# 04_PMIC2.net
KiCad netlist of a schematic drawn in Altium Designer
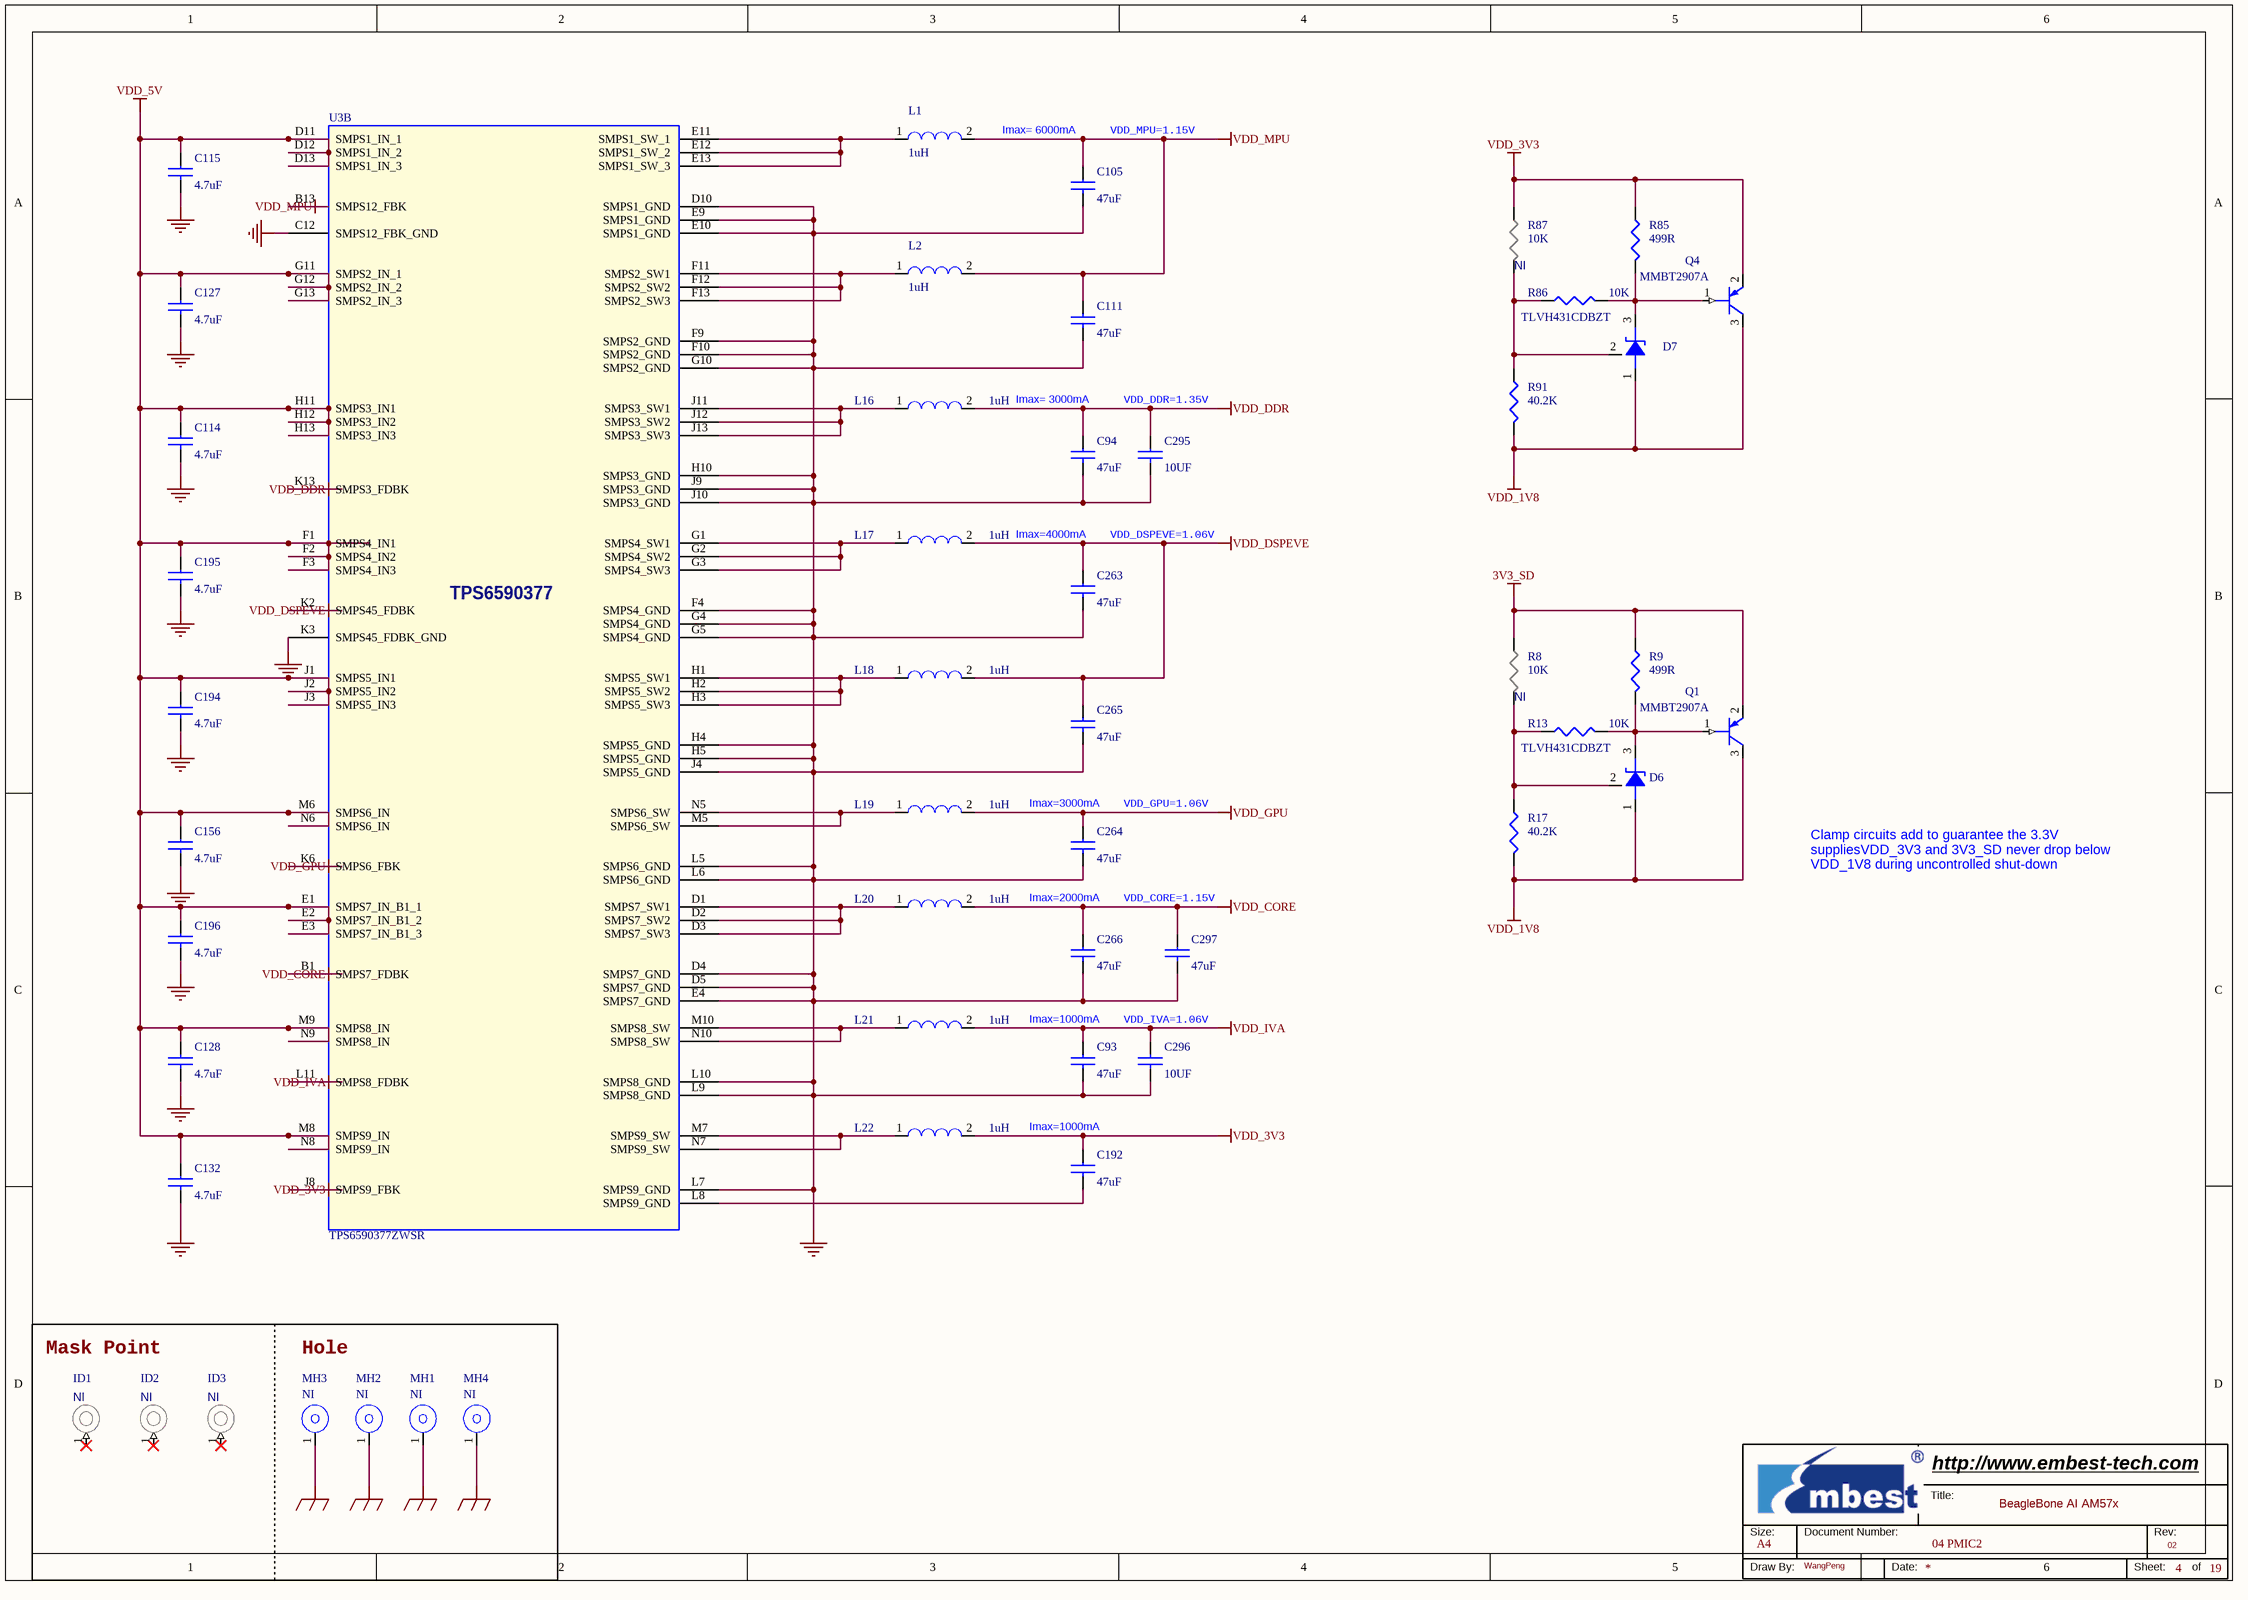
[diagram p0: 04 PMIC2.SchDoc]

(export (version "E")
  (design (tool "Eeschema 10.0.6"))
  (components
    (comp (ref "C93")
      (value "47uF")
      (footprint "C0805")
      (description "CAP,47UF,+/-20%,X5R,6.3V,SMD0805")
      (fields
        (field (name "MANUFACTURER PART NUMBER") "GRM21BR60J476ME15L")
        (field (name "MANUFACTURER") "MURATA")
      )
      (libsource (lib "*") (part "C"))
    )
    (comp (ref "C94")
      (value "47uF")
      (footprint "C0805")
      (description "CAP,47UF,+/-20%,X5R,6.3V,SMD0805")
      (fields
        (field (name "MANUFACTURER PART NUMBER") "GRM21BR60J476ME15L")
        (field (name "MANUFACTURER") "MURATA")
      )
      (libsource (lib "*") (part "C"))
    )
    (comp (ref "C105")
      (value "47uF")
      (footprint "C0805")
      (description "CAP,47UF,+/-20%,X5R,6.3V,SMD0805")
      (fields
        (field (name "MANUFACTURER PART NUMBER") "GRM21BR60J476ME15L")
        (field (name "MANUFACTURER") "MURATA")
      )
      (libsource (lib "*") (part "C"))
    )
    (comp (ref "C111")
      (value "47uF")
      (footprint "C0805")
      (description "CAP,47UF,+/-20%,X5R,6.3V,SMD0805")
      (fields
        (field (name "MANUFACTURER PART NUMBER") "GRM21BR60J476ME15L")
        (field (name "MANUFACTURER") "MURATA")
      )
      (libsource (lib "*") (part "C"))
    )
    (comp (ref "C114")
      (value "4.7uF")
      (footprint "C0603")
      (description "CAP,4.7UF,+/-10%,X5R,16V,SMD0603")
      (fields
        (field (name "MANUFACTURER PART NUMBER") "GRM188R61C475KAAJD")
        (field (name "MANUFACTURER") "Murata")
        (field (name "DATASHEET") "Y:\\新K3系统物料datasheet\\[1003_1004]capacitor-resistor 电容、电阻\\1004001100127 GRM188R61C475KAAJD murata.pdf")
      )
      (libsource (lib "*") (part "C"))
    )
    (comp (ref "C115")
      (value "4.7uF")
      (footprint "C0603")
      (description "CAP,4.7UF,+/-10%,X5R,16V,SMD0603")
      (fields
        (field (name "MANUFACTURER PART NUMBER") "GRM188R61C475KAAJD")
        (field (name "MANUFACTURER") "Murata")
        (field (name "DATASHEET") "Y:\\新K3系统物料datasheet\\[1003_1004]capacitor-resistor 电容、电阻\\1004001100127 GRM188R61C475KAAJD murata.pdf")
      )
      (libsource (lib "*") (part "C"))
    )
    (comp (ref "C127")
      (value "4.7uF")
      (footprint "C0603")
      (description "CAP,4.7UF,+/-10%,X5R,16V,SMD0603")
      (fields
        (field (name "MANUFACTURER") "Murata")
        (field (name "MANUFACTURER PART NUMBER") "GRM188R61C475KAAJD")
        (field (name "DATASHEET") "Y:\\新K3系统物料datasheet\\[1003_1004]capacitor-resistor 电容、电阻\\1004001100127 GRM188R61C475KAAJD murata.pdf")
      )
      (libsource (lib "*") (part "C"))
    )
    (comp (ref "C128")
      (value "4.7uF")
      (footprint "C0603")
      (description "CAP,4.7UF,+/-10%,X5R,16V,SMD0603")
      (fields
        (field (name "MANUFACTURER") "Murata")
        (field (name "MANUFACTURER PART NUMBER") "GRM188R61C475KAAJD")
        (field (name "DATASHEET") "Y:\\新K3系统物料datasheet\\[1003_1004]capacitor-resistor 电容、电阻\\1004001100127 GRM188R61C475KAAJD murata.pdf")
      )
      (libsource (lib "*") (part "C"))
    )
    (comp (ref "C132")
      (value "4.7uF")
      (footprint "C0603")
      (description "CAP,4.7UF,+/-10%,X5R,16V,SMD0603")
      (fields
        (field (name "MANUFACTURER PART NUMBER") "GRM188R61C475KAAJD")
        (field (name "MANUFACTURER") "Murata")
        (field (name "DATASHEET") "Y:\\新K3系统物料datasheet\\[1003_1004]capacitor-resistor 电容、电阻\\1004001100127 GRM188R61C475KAAJD murata.pdf")
      )
      (libsource (lib "*") (part "C"))
    )
    (comp (ref "C156")
      (value "4.7uF")
      (footprint "C0603")
      (description "CAP,4.7UF,+/-10%,X5R,16V,SMD0603")
      (fields
        (field (name "MANUFACTURER") "Murata")
        (field (name "MANUFACTURER PART NUMBER") "GRM188R61C475KAAJD")
        (field (name "DATASHEET") "Y:\\新K3系统物料datasheet\\[1003_1004]capacitor-resistor 电容、电阻\\1004001100127 GRM188R61C475KAAJD murata.pdf")
      )
      (libsource (lib "*") (part "C"))
    )
    (comp (ref "C192")
      (value "47uF")
      (footprint "C0805")
      (description "CAP,47UF,+/-20%,X5R,6.3V,SMD0805")
      (fields
        (field (name "MANUFACTURER PART NUMBER") "GRM21BR60J476ME15L")
        (field (name "MANUFACTURER") "MURATA")
      )
      (libsource (lib "*") (part "C"))
    )
    (comp (ref "C194")
      (value "4.7uF")
      (footprint "C0603")
      (description "CAP,4.7UF,+/-10%,X5R,16V,SMD0603")
      (fields
        (field (name "MANUFACTURER") "Murata")
        (field (name "MANUFACTURER PART NUMBER") "GRM188R61C475KAAJD")
        (field (name "DATASHEET") "Y:\\新K3系统物料datasheet\\[1003_1004]capacitor-resistor 电容、电阻\\1004001100127 GRM188R61C475KAAJD murata.pdf")
      )
      (libsource (lib "*") (part "C"))
    )
    (comp (ref "C195")
      (value "4.7uF")
      (footprint "C0603")
      (description "CAP,4.7UF,+/-10%,X5R,16V,SMD0603")
      (fields
        (field (name "MANUFACTURER") "Murata")
        (field (name "MANUFACTURER PART NUMBER") "GRM188R61C475KAAJD")
        (field (name "DATASHEET") "Y:\\新K3系统物料datasheet\\[1003_1004]capacitor-resistor 电容、电阻\\1004001100127 GRM188R61C475KAAJD murata.pdf")
      )
      (libsource (lib "*") (part "C"))
    )
    (comp (ref "C196")
      (value "4.7uF")
      (footprint "C0603")
      (description "CAP,4.7UF,+/-10%,X5R,16V,SMD0603")
      (fields
        (field (name "MANUFACTURER") "Murata")
        (field (name "MANUFACTURER PART NUMBER") "GRM188R61C475KAAJD")
        (field (name "DATASHEET") "Y:\\新K3系统物料datasheet\\[1003_1004]capacitor-resistor 电容、电阻\\1004001100127 GRM188R61C475KAAJD murata.pdf")
      )
      (libsource (lib "*") (part "C"))
    )
    (comp (ref "C263")
      (value "47uF")
      (footprint "C0805")
      (description "CAP,47UF,+/-20%,X5R,6.3V,SMD0805")
      (fields
        (field (name "MANUFACTURER PART NUMBER") "GRM21BR60J476ME15L")
        (field (name "MANUFACTURER") "MURATA")
      )
      (libsource (lib "*") (part "C"))
    )
    (comp (ref "C264")
      (value "47uF")
      (footprint "C0805")
      (description "CAP,47UF,+/-20%,X5R,6.3V,SMD0805")
      (fields
        (field (name "MANUFACTURER PART NUMBER") "GRM21BR60J476ME15L")
        (field (name "MANUFACTURER") "MURATA")
      )
      (libsource (lib "*") (part "C"))
    )
    (comp (ref "C265")
      (value "47uF")
      (footprint "C0805")
      (description "CAP,47UF,+/-20%,X5R,6.3V,SMD0805")
      (fields
        (field (name "MANUFACTURER PART NUMBER") "GRM21BR60J476ME15L")
        (field (name "MANUFACTURER") "MURATA")
      )
      (libsource (lib "*") (part "C"))
    )
    (comp (ref "C266")
      (value "47uF")
      (footprint "C0805")
      (description "CAP,47UF,+/-20%,X5R,6.3V,SMD0805")
      (fields
        (field (name "MANUFACTURER PART NUMBER") "GRM21BR60J476ME15L")
        (field (name "MANUFACTURER") "MURATA")
      )
      (libsource (lib "*") (part "C"))
    )
    (comp (ref "C295")
      (value "10UF")
      (footprint "C0603")
      (description "CAP,10UF,+/-10%,X5R,10V,SMD0603")
      (fields
        (field (name "MANUFACTURER") "Murata")
        (field (name "MANUFACTURER PART NUMBER") "GRM188R61A106KE69D")
        (field (name "DATASHEET") "Y:\\新K3系统物料datasheet\\[1003_1004]capacitor-resistor 电容、电阻\\1004001100129T2 C1608X5R1A106M.pdf")
      )
      (libsource (lib "*") (part "C"))
    )
    (comp (ref "C296")
      (value "10UF")
      (footprint "C0402")
      (description "CAP,10UF,+/-20%,X5R,6.3V,SMD0402")
      (fields
        (field (name "MANUFACTURER PART NUMBER") "CC0402MRX5R5BB106")
        (field (name "MANUFACTURER") "Yageo")
      )
      (libsource (lib "*") (part "C"))
    )
    (comp (ref "C297")
      (value "47uF")
      (footprint "C0805")
      (description "CAP,47UF,+/-20%,X5R,6.3V,SMD0805")
      (fields
        (field (name "MANUFACTURER PART NUMBER") "GRM21BR60J476ME15L")
        (field (name "MANUFACTURER") "MURATA")
      )
      (libsource (lib "*") (part "C"))
    )
    (comp (ref "D6")
      (value "TLVH431CDBZT")
      (footprint "sot95p240x120-3n")
      (description "IC,Low-Voltage Adjustable Precision Shunt Regulators")
      (fields (field (name "MANUFACTURER") "TI"))
      (libsource (lib "*") (part "DIODE ZENER_3"))
    )
    (comp (ref "D7")
      (value "TLVH431CDBZT")
      (footprint "sot95p240x120-3n")
      (description "IC,Low-Voltage Adjustable Precision Shunt Regulators")
      (fields (field (name "MANUFACTURER") "TI"))
      (libsource (lib "*") (part "DIODE ZENER_3"))
    )
    (comp (ref "ID1")
      (value "NI")
      (footprint "FD40")
      (description "MARK  point,DIA 40mil")
      (fields (field (name "ASSY") "NI"))
      (libsource (lib "*") (part "MARK POINT"))
    )
    (comp (ref "ID2")
      (value "NI")
      (footprint "FD40")
      (description "MARK  point,DIA 40mil")
      (fields (field (name "ASSY") "NI"))
      (libsource (lib "*") (part "MARK POINT"))
    )
    (comp (ref "ID3")
      (value "NI")
      (footprint "FD40")
      (description "MARK  point,DIA 40mil")
      (fields (field (name "ASSY") "NI"))
      (libsource (lib "*") (part "MARK POINT"))
    )
    (comp (ref "L1")
      (value "1uH")
      (footprint "L40X40_B")
      (description "Power Inductor,Magnetic shielded,1uH,idc4.5A,27mohm,4.3x4.0x2.0mm,20%,SMD,TR")
      (fields
        (field (name "MANUFACTURER PART NUMBER") "SP04O203M1U")
        (field (name "MANUFACTURER") "GAUSSTEK")
        (field (name "DATASHEET") "Y:\\新K3系统物料datasheet\\[1005]beads-inductors 磁珠、电感\\1005004100077 S-英蓓特SP04O203M1U.pdf")
      )
      (libsource (lib "*") (part "L"))
    )
    (comp (ref "L2")
      (value "1uH")
      (footprint "L40X40_B")
      (description "Power Inductor,Magnetic shielded,1uH,idc4.5A,27mohm,4.3x4.0x2.0mm,20%,SMD,TR")
      (fields
        (field (name "MANUFACTURER") "GAUSSTEK")
        (field (name "MANUFACTURER PART NUMBER") "SP04O203M1U")
        (field (name "DATASHEET") "Y:\\新K3系统物料datasheet\\[1005]beads-inductors 磁珠、电感\\1005004100077 S-英蓓特SP04O203M1U.pdf")
      )
      (libsource (lib "*") (part "L"))
    )
    (comp (ref "L16")
      (value "1uH")
      (footprint "INDPW250X200X105N")
      (fields
        (field (name "MANUFACTURER") "Gausstek")
        (field (name "MANUFACTURER PART NUMBER") "DI20A102M1U")
        (field (name "DATASHEET") "Y:\\新K3系统物料datasheet\\[1005]beads-inductors 磁珠、电感\\1005001100194 DI20A102M1U.pdf")
      )
      (libsource (lib "*") (part "L"))
    )
    (comp (ref "L17")
      (value "1uH")
      (footprint "INDPW250X200X105N")
      (fields
        (field (name "MANUFACTURER PART NUMBER") "DI20A102M1U")
        (field (name "MANUFACTURER") "Gausstek")
        (field (name "DATASHEET") "Y:\\新K3系统物料datasheet\\[1005]beads-inductors 磁珠、电感\\1005001100194 DI20A102M1U.pdf")
      )
      (libsource (lib "*") (part "L"))
    )
    (comp (ref "L18")
      (value "1uH")
      (footprint "INDPW250X200X105N")
      (fields
        (field (name "MANUFACTURER") "Gausstek")
        (field (name "MANUFACTURER PART NUMBER") "DI20A102M1U")
        (field (name "DATASHEET") "Y:\\新K3系统物料datasheet\\[1005]beads-inductors 磁珠、电感\\1005001100194 DI20A102M1U.pdf")
      )
      (libsource (lib "*") (part "L"))
    )
    (comp (ref "L19")
      (value "1uH")
      (footprint "INDPW250X200X105N")
      (fields
        (field (name "MANUFACTURER PART NUMBER") "DI20A102M1U")
        (field (name "MANUFACTURER") "Gausstek")
        (field (name "DATASHEET") "Y:\\新K3系统物料datasheet\\[1005]beads-inductors 磁珠、电感\\1005001100194 DI20A102M1U.pdf")
      )
      (libsource (lib "*") (part "L"))
    )
    (comp (ref "L20")
      (value "1uH")
      (footprint "INDPW250X200X105N")
      (fields
        (field (name "MANUFACTURER") "Gausstek")
        (field (name "MANUFACTURER PART NUMBER") "DI20A102M1U")
        (field (name "DATASHEET") "Y:\\新K3系统物料datasheet\\[1005]beads-inductors 磁珠、电感\\1005001100194 DI20A102M1U.pdf")
      )
      (libsource (lib "*") (part "L"))
    )
    (comp (ref "L21")
      (value "1uH")
      (footprint "INDPW250X200X105N")
      (fields
        (field (name "MANUFACTURER PART NUMBER") "DI20A102M1U")
        (field (name "MANUFACTURER") "Gausstek")
        (field (name "DATASHEET") "Y:\\新K3系统物料datasheet\\[1005]beads-inductors 磁珠、电感\\1005001100194 DI20A102M1U.pdf")
      )
      (libsource (lib "*") (part "L"))
    )
    (comp (ref "L22")
      (value "1uH")
      (footprint "INDPW250X200X105N")
      (fields
        (field (name "MANUFACTURER") "Gausstek")
        (field (name "MANUFACTURER PART NUMBER") "DI20A102M1U")
        (field (name "DATASHEET") "Y:\\新K3系统物料datasheet\\[1005]beads-inductors 磁珠、电感\\1005001100194 DI20A102M1U.pdf")
      )
      (libsource (lib "*") (part "L"))
    )
    (comp (ref "MH1")
      (value "NI")
      (footprint "MTGH200C125D_PL")
      (description "Plated hole,Circle,DAI 4.445MM ,VIA 3.175MM")
      (libsource (lib "*") (part "METALLIC HOLE"))
    )
    (comp (ref "MH2")
      (value "NI")
      (footprint "MTGH200C125D_PL")
      (description "Plated hole,Circle,DAI 4.445MM ,VIA 3.175MM")
      (libsource (lib "*") (part "METALLIC HOLE"))
    )
    (comp (ref "MH3")
      (value "NI")
      (footprint "MTGH200C125D_PL")
      (description "Plated hole,Circle,DAI 4.445MM ,VIA 3.175MM")
      (libsource (lib "*") (part "METALLIC HOLE"))
    )
    (comp (ref "MH4")
      (value "NI")
      (footprint "MTGH200C125D_PL")
      (description "Plated hole,Circle,DAI 4.445MM ,VIA 3.175MM")
      (libsource (lib "*") (part "METALLIC HOLE"))
    )
    (comp (ref "Q1")
      (value "MMBT2907A")
      (footprint "SOT23_123")
      (description "Transistor,PNP,MMBT2907A-7-F,60V,600MA,SOT-23,SMD")
      (fields
        (field (name "MANUFACTURER") "Diodes")
        (field (name "MANUFACTURER PART NUMBER") "MMBT2907A-7-F")
        (field (name "DATASHEET") "Y:\\新K3系统物料datasheet\\[1006002~013]diodes-transistors 二三极管\\1006012100001 Diodes MMBT2907A-7-F.pdf")
      )
      (libsource (lib "*") (part "PNP"))
    )
    (comp (ref "Q4")
      (value "MMBT2907A")
      (footprint "SOT23_123")
      (description "Transistor,PNP,MMBT2907A-7-F,60V,600MA,SOT-23,SMD")
      (fields
        (field (name "MANUFACTURER") "Diodes")
        (field (name "MANUFACTURER PART NUMBER") "MMBT2907A-7-F")
        (field (name "DATASHEET") "Y:\\新K3系统物料datasheet\\[1006002~013]diodes-transistors 二三极管\\1006012100001 Diodes MMBT2907A-7-F.pdf")
      )
      (libsource (lib "*") (part "PNP"))
    )
    (comp (ref "R8")
      (value "10K")
      (footprint "R0402")
      (description "RES,10K,+/-1%,1/16W,SMD0402")
      (fields
        (field (name "ASSY") "NI")
        (field (name "MANUFACTURER PART NUMBER") "RC0402FR-0710KL")
        (field (name "MANUFACTURER") "YAGEO")
      )
      (libsource (lib "*") (part "R"))
    )
    (comp (ref "R9")
      (value "499R")
      (footprint "R0402")
      (description "RES,499R,+/-1%,1/16W,SMD0402")
      (fields
        (field (name "MANUFACTURER") "YAGEO")
        (field (name "MANUFACTURER PART NUMBER") "RC0402FR-07499RL")
      )
      (libsource (lib "*") (part "R"))
    )
    (comp (ref "R13")
      (value "10K")
      (footprint "R0402")
      (description "RES,10K,+/-1%,1/16W,SMD0402")
      (fields
        (field (name "MANUFACTURER PART NUMBER") "RC0402FR-0710KL")
        (field (name "MANUFACTURER") "YAGEO")
      )
      (libsource (lib "*") (part "R"))
    )
    (comp (ref "R17")
      (value "40.2K")
      (footprint "R0402")
      (description "RES,40K2,+/-1%,1/16W,SMD0402")
      (fields
        (field (name "MANUFACTURER") "YAGEO")
        (field (name "MANUFACTURER PART NUMBER") "RC0402FR-0740K2L")
      )
      (libsource (lib "*") (part "R"))
    )
    (comp (ref "R85")
      (value "499R")
      (footprint "R0402")
      (description "RES,499R,+/-1%,1/16W,SMD0402")
      (fields
        (field (name "MANUFACTURER") "YAGEO")
        (field (name "MANUFACTURER PART NUMBER") "RC0402FR-07499RL")
      )
      (libsource (lib "*") (part "R"))
    )
    (comp (ref "R86")
      (value "10K")
      (footprint "R0402")
      (description "RES,10K,+/-1%,1/16W,SMD0402")
      (fields
        (field (name "MANUFACTURER PART NUMBER") "RC0402FR-0710KL")
        (field (name "MANUFACTURER") "YAGEO")
      )
      (libsource (lib "*") (part "R"))
    )
    (comp (ref "R87")
      (value "10K")
      (footprint "R0402")
      (description "RES,10K,+/-1%,1/16W,SMD0402")
      (fields
        (field (name "ASSY") "NI")
        (field (name "MANUFACTURER PART NUMBER") "RC0402FR-0710KL")
        (field (name "MANUFACTURER") "YAGEO")
      )
      (libsource (lib "*") (part "R"))
    )
    (comp (ref "R91")
      (value "40.2K")
      (footprint "R0402")
      (description "RES,40K2,+/-1%,1/16W,SMD0402")
      (fields
        (field (name "MANUFACTURER") "YAGEO")
        (field (name "MANUFACTURER PART NUMBER") "RC0402FR-0740K2L")
      )
      (libsource (lib "*") (part "R"))
    )
    (comp (ref "U3")
      (value "TPS6590377ZWSR")
      (footprint "bga12x12-169-55m")
      (description "IC TPS659037 Power Management Unit (PMU) for Processor NFBGA-169 SMD")
      (fields
        (field (name "MANUFACTURER") "TI")
        (field (name "DATASHEET") "Y:\\新K3系统物料datasheet\\[1002]IC 集成电路\\1002004100230 [TPS6590377ZWSR] tps659037.pdf")
      )
      (libsource (lib "*") (part "TPS659037"))
    )
  )
  (nets
    (net (code "1") (name "3V3_SD") (class "Default")
      (node (ref "Q1") (pin "2") (pinfunction "E_2") (pintype "passive"))
      (node (ref "R8") (pin "1") (pinfunction "1_1") (pintype "passive"))
      (node (ref "R9") (pin "1") (pinfunction "1_1") (pintype "passive"))
    )
    (net (code "2") (name "GND") (class "Default")
      (node (ref "C105") (pin "2") (pinfunction "2_2") (pintype "passive"))
      (node (ref "C111") (pin "2") (pinfunction "2_2") (pintype "passive"))
      (node (ref "C114") (pin "2") (pinfunction "2_2") (pintype "passive"))
      (node (ref "C115") (pin "2") (pinfunction "2_2") (pintype "passive"))
      (node (ref "C127") (pin "2") (pinfunction "2_2") (pintype "passive"))
      (node (ref "C128") (pin "2") (pinfunction "2_2") (pintype "passive"))
      (node (ref "C132") (pin "2") (pinfunction "2_2") (pintype "passive"))
      (node (ref "C156") (pin "2") (pinfunction "2_2") (pintype "passive"))
      (node (ref "C194") (pin "2") (pinfunction "2_2") (pintype "passive"))
      (node (ref "C195") (pin "2") (pinfunction "2_2") (pintype "passive"))
      (node (ref "C196") (pin "2") (pinfunction "2_2") (pintype "passive"))
      (node (ref "C263") (pin "2") (pinfunction "2_2") (pintype "passive"))
      (node (ref "C264") (pin "2") (pinfunction "2_2") (pintype "passive"))
      (node (ref "C265") (pin "2") (pinfunction "2_2") (pintype "passive"))
      (node (ref "C266") (pin "2") (pinfunction "2_2") (pintype "passive"))
      (node (ref "C295") (pin "2") (pinfunction "2_2") (pintype "passive"))
      (node (ref "C296") (pin "2") (pinfunction "2_2") (pintype "passive"))
      (node (ref "C297") (pin "2") (pinfunction "2_2") (pintype "passive"))
      (node (ref "C93") (pin "2") (pinfunction "2_2") (pintype "passive"))
      (node (ref "C94") (pin "2") (pinfunction "2_2") (pintype "passive"))
      (node (ref "U3") (pin "C12") (pinfunction "SMPS12_FBK_GND_C12") (pintype "passive"))
      (node (ref "U3") (pin "D10") (pinfunction "SMPS1_GND_D10") (pintype "power_in"))
      (node (ref "U3") (pin "D4") (pinfunction "SMPS7_GND_D4") (pintype "power_in"))
      (node (ref "U3") (pin "D5") (pinfunction "SMPS7_GND_D5") (pintype "power_in"))
      (node (ref "U3") (pin "E10") (pinfunction "SMPS1_GND_E10") (pintype "power_in"))
      (node (ref "U3") (pin "E4") (pinfunction "SMPS7_GND_E4") (pintype "power_in"))
      (node (ref "U3") (pin "E9") (pinfunction "SMPS1_GND_E9") (pintype "power_in"))
      (node (ref "U3") (pin "F10") (pinfunction "SMPS2_GND_F10") (pintype "power_in"))
      (node (ref "U3") (pin "F4") (pinfunction "SMPS4_GND_F4") (pintype "power_in"))
      (node (ref "U3") (pin "F9") (pinfunction "SMPS2_GND_F9") (pintype "power_in"))
      (node (ref "U3") (pin "G10") (pinfunction "SMPS2_GND_G10") (pintype "power_in"))
      (node (ref "U3") (pin "G4") (pinfunction "SMPS4_GND_G4") (pintype "power_in"))
      (node (ref "U3") (pin "G5") (pinfunction "SMPS4_GND_G5") (pintype "power_in"))
      (node (ref "U3") (pin "H10") (pinfunction "SMPS3_GND_H10") (pintype "power_in"))
      (node (ref "U3") (pin "H4") (pinfunction "SMPS5_GND_H4") (pintype "power_in"))
      (node (ref "U3") (pin "H5") (pinfunction "SMPS5_GND_H5") (pintype "power_in"))
      (node (ref "U3") (pin "J10") (pinfunction "SMPS3_GND_J10") (pintype "power_in"))
      (node (ref "U3") (pin "J4") (pinfunction "SMPS5_GND_J4") (pintype "power_in"))
      (node (ref "U3") (pin "J9") (pinfunction "SMPS3_GND_J9") (pintype "power_in"))
      (node (ref "U3") (pin "K3") (pinfunction "SMPS45_FDBK_GND_K3") (pintype "passive"))
      (node (ref "U3") (pin "L10") (pinfunction "SMPS8_GND_L10") (pintype "power_in"))
      (node (ref "U3") (pin "L5") (pinfunction "SMPS6_GND_L5") (pintype "power_in"))
      (node (ref "U3") (pin "L6") (pinfunction "SMPS6_GND_L6") (pintype "power_in"))
      (node (ref "U3") (pin "L7") (pinfunction "SMPS9_GND_L7") (pintype "power_in"))
      (node (ref "U3") (pin "L9") (pinfunction "SMPS8_GND_L9") (pintype "power_in"))
    )
    (net (code "3") (name "GND_EARTH") (class "Default")
      (node (ref "MH1") (pin "1") (pinfunction "1_1") (pintype "passive"))
      (node (ref "MH2") (pin "1") (pinfunction "1_1") (pintype "passive"))
      (node (ref "MH3") (pin "1") (pinfunction "1_1") (pintype "passive"))
      (node (ref "MH4") (pin "1") (pinfunction "1_1") (pintype "passive"))
    )
    (net (code "4") (name "Net-(C192-Pad2)") (class "Default")
      (node (ref "C192") (pin "2") (pinfunction "2_2") (pintype "passive"))
      (node (ref "U3") (pin "L8") (pinfunction "SMPS9_GND_L8") (pintype "power_in"))
    )
    (net (code "5") (name "Net-(D6-K)") (class "Default")
      (node (ref "D6") (pin "3") (pinfunction "K_3") (pintype "passive"))
      (node (ref "Q1") (pin "1") (pinfunction "B_1") (pintype "input"))
      (node (ref "R13") (pin "2") (pinfunction "2_2") (pintype "passive"))
      (node (ref "R9") (pin "2") (pinfunction "2_2") (pintype "passive"))
    )
    (net (code "6") (name "Net-(D6-NC)") (class "Default")
      (node (ref "D6") (pin "2") (pinfunction "NC_2") (pintype "passive"))
      (node (ref "R13") (pin "1") (pinfunction "1_1") (pintype "passive"))
      (node (ref "R17") (pin "1") (pinfunction "1_1") (pintype "passive"))
      (node (ref "R8") (pin "2") (pinfunction "2_2") (pintype "passive"))
    )
    (net (code "7") (name "Net-(D7-K)") (class "Default")
      (node (ref "D7") (pin "3") (pinfunction "K_3") (pintype "passive"))
      (node (ref "Q4") (pin "1") (pinfunction "B_1") (pintype "input"))
      (node (ref "R85") (pin "2") (pinfunction "2_2") (pintype "passive"))
      (node (ref "R86") (pin "2") (pinfunction "2_2") (pintype "passive"))
    )
    (net (code "8") (name "Net-(D7-NC)") (class "Default")
      (node (ref "D7") (pin "2") (pinfunction "NC_2") (pintype "passive"))
      (node (ref "R86") (pin "1") (pinfunction "1_1") (pintype "passive"))
      (node (ref "R87") (pin "2") (pinfunction "2_2") (pintype "passive"))
      (node (ref "R91") (pin "1") (pinfunction "1_1") (pintype "passive"))
    )
    (net (code "9") (name "Net-(L19-Pad1)") (class "Default")
      (node (ref "L19") (pin "1") (pinfunction "1_1") (pintype "passive"))
      (node (ref "U3") (pin "M5") (pinfunction "SMPS6_SW_M5") (pintype "power_in"))
      (node (ref "U3") (pin "N5") (pinfunction "SMPS6_SW_N5") (pintype "power_in"))
    )
    (net (code "10") (name "Net-(L21-Pad1)") (class "Default")
      (node (ref "L21") (pin "1") (pinfunction "1_1") (pintype "passive"))
      (node (ref "U3") (pin "M10") (pinfunction "SMPS8_SW_M10") (pintype "power_in"))
      (node (ref "U3") (pin "N10") (pinfunction "SMPS8_SW_N10") (pintype "power_in"))
    )
    (net (code "11") (name "Net-(L22-Pad1)") (class "Default")
      (node (ref "L22") (pin "1") (pinfunction "1_1") (pintype "passive"))
      (node (ref "U3") (pin "M7") (pinfunction "SMPS9_SW_M7") (pintype "power_in"))
      (node (ref "U3") (pin "N7") (pinfunction "SMPS9_SW_N7") (pintype "power_in"))
    )
    (net (code "12") (name "Net-(U3B-SMPS1_SW_1)") (class "Default")
      (node (ref "L1") (pin "1") (pinfunction "1_1") (pintype "passive"))
      (node (ref "U3") (pin "E11") (pinfunction "SMPS1_SW_1_E11") (pintype "passive"))
      (node (ref "U3") (pin "E12") (pinfunction "SMPS1_SW_2_E12") (pintype "passive"))
      (node (ref "U3") (pin "E13") (pinfunction "SMPS1_SW_3_E13") (pintype "passive"))
    )
    (net (code "13") (name "Net-(U3B-SMPS2_SW1)") (class "Default")
      (node (ref "L2") (pin "1") (pinfunction "1_1") (pintype "passive"))
      (node (ref "U3") (pin "F11") (pinfunction "SMPS2_SW1_F11") (pintype "passive"))
      (node (ref "U3") (pin "F12") (pinfunction "SMPS2_SW2_F12") (pintype "passive"))
      (node (ref "U3") (pin "F13") (pinfunction "SMPS2_SW3_F13") (pintype "passive"))
    )
    (net (code "14") (name "Net-(U3B-SMPS3_SW1)") (class "Default")
      (node (ref "L16") (pin "1") (pinfunction "1_1") (pintype "passive"))
      (node (ref "U3") (pin "J11") (pinfunction "SMPS3_SW1_J11") (pintype "passive"))
      (node (ref "U3") (pin "J12") (pinfunction "SMPS3_SW2_J12") (pintype "passive"))
      (node (ref "U3") (pin "J13") (pinfunction "SMPS3_SW3_J13") (pintype "passive"))
    )
    (net (code "15") (name "Net-(U3B-SMPS4_SW1)") (class "Default")
      (node (ref "L17") (pin "1") (pinfunction "1_1") (pintype "passive"))
      (node (ref "U3") (pin "G1") (pinfunction "SMPS4_SW1_G1") (pintype "passive"))
      (node (ref "U3") (pin "G2") (pinfunction "SMPS4_SW2_G2") (pintype "passive"))
      (node (ref "U3") (pin "G3") (pinfunction "SMPS4_SW3_G3") (pintype "passive"))
    )
    (net (code "16") (name "Net-(U3B-SMPS5_SW1)") (class "Default")
      (node (ref "L18") (pin "1") (pinfunction "1_1") (pintype "passive"))
      (node (ref "U3") (pin "H1") (pinfunction "SMPS5_SW1_H1") (pintype "passive"))
      (node (ref "U3") (pin "H2") (pinfunction "SMPS5_SW2_H2") (pintype "passive"))
      (node (ref "U3") (pin "H3") (pinfunction "SMPS5_SW3_H3") (pintype "passive"))
    )
    (net (code "17") (name "Net-(U3B-SMPS7_SW1)") (class "Default")
      (node (ref "L20") (pin "1") (pinfunction "1_1") (pintype "passive"))
      (node (ref "U3") (pin "D1") (pinfunction "SMPS7_SW1_D1") (pintype "power_in"))
      (node (ref "U3") (pin "D2") (pinfunction "SMPS7_SW2_D2") (pintype "power_in"))
      (node (ref "U3") (pin "D3") (pinfunction "SMPS7_SW3_D3") (pintype "power_in"))
    )
    (net (code "18") (name "VDD_1V8") (class "Default")
      (node (ref "D6") (pin "1") (pinfunction "A_1") (pintype "passive"))
      (node (ref "D7") (pin "1") (pinfunction "A_1") (pintype "passive"))
      (node (ref "Q1") (pin "3") (pinfunction "C_3") (pintype "passive"))
      (node (ref "Q4") (pin "3") (pinfunction "C_3") (pintype "passive"))
      (node (ref "R17") (pin "2") (pinfunction "2_2") (pintype "passive"))
      (node (ref "R91") (pin "2") (pinfunction "2_2") (pintype "passive"))
    )
    (net (code "19") (name "VDD_3V3") (class "Default")
      (node (ref "C192") (pin "1") (pinfunction "1_1") (pintype "passive"))
      (node (ref "L22") (pin "2") (pinfunction "2_2") (pintype "passive"))
      (node (ref "Q4") (pin "2") (pinfunction "E_2") (pintype "passive"))
      (node (ref "R85") (pin "1") (pinfunction "1_1") (pintype "passive"))
      (node (ref "R87") (pin "1") (pinfunction "1_1") (pintype "passive"))
      (node (ref "U3") (pin "J8") (pinfunction "SMPS9_FBK_J8") (pintype "passive"))
    )
    (net (code "20") (name "VDD_5V") (class "Default")
      (node (ref "C114") (pin "1") (pinfunction "1_1") (pintype "passive"))
      (node (ref "C115") (pin "1") (pinfunction "1_1") (pintype "passive"))
      (node (ref "C127") (pin "1") (pinfunction "1_1") (pintype "passive"))
      (node (ref "C128") (pin "1") (pinfunction "1_1") (pintype "passive"))
      (node (ref "C132") (pin "1") (pinfunction "1_1") (pintype "passive"))
      (node (ref "C156") (pin "1") (pinfunction "1_1") (pintype "passive"))
      (node (ref "C194") (pin "1") (pinfunction "1_1") (pintype "passive"))
      (node (ref "C195") (pin "1") (pinfunction "1_1") (pintype "passive"))
      (node (ref "C196") (pin "1") (pinfunction "1_1") (pintype "passive"))
      (node (ref "U3") (pin "D11") (pinfunction "SMPS1_IN_1_D11") (pintype "passive"))
      (node (ref "U3") (pin "D12") (pinfunction "SMPS1_IN_2_D12") (pintype "passive"))
      (node (ref "U3") (pin "D13") (pinfunction "SMPS1_IN_3_D13") (pintype "passive"))
      (node (ref "U3") (pin "E1") (pinfunction "SMPS7_IN_B1_1_E1") (pintype "power_in"))
      (node (ref "U3") (pin "E2") (pinfunction "SMPS7_IN_B1_2_E2") (pintype "power_in"))
      (node (ref "U3") (pin "E3") (pinfunction "SMPS7_IN_B1_3_E3") (pintype "power_in"))
      (node (ref "U3") (pin "F1") (pinfunction "SMPS4_IN1_F1") (pintype "passive"))
      (node (ref "U3") (pin "F2") (pinfunction "SMPS4_IN2_F2") (pintype "passive"))
      (node (ref "U3") (pin "F3") (pinfunction "SMPS4_IN3_F3") (pintype "passive"))
      (node (ref "U3") (pin "G11") (pinfunction "SMPS2_IN_1_G11") (pintype "passive"))
      (node (ref "U3") (pin "G12") (pinfunction "SMPS2_IN_2_G12") (pintype "passive"))
      (node (ref "U3") (pin "G13") (pinfunction "SMPS2_IN_3_G13") (pintype "passive"))
      (node (ref "U3") (pin "H11") (pinfunction "SMPS3_IN1_H11") (pintype "passive"))
      (node (ref "U3") (pin "H12") (pinfunction "SMPS3_IN2_H12") (pintype "passive"))
      (node (ref "U3") (pin "H13") (pinfunction "SMPS3_IN3_H13") (pintype "passive"))
      (node (ref "U3") (pin "J1") (pinfunction "SMPS5_IN1_J1") (pintype "passive"))
      (node (ref "U3") (pin "J2") (pinfunction "SMPS5_IN2_J2") (pintype "passive"))
      (node (ref "U3") (pin "J3") (pinfunction "SMPS5_IN3_J3") (pintype "passive"))
      (node (ref "U3") (pin "M6") (pinfunction "SMPS6_IN_M6") (pintype "power_in"))
      (node (ref "U3") (pin "M8") (pinfunction "SMPS9_IN_M8") (pintype "power_in"))
      (node (ref "U3") (pin "M9") (pinfunction "SMPS8_IN_M9") (pintype "power_in"))
      (node (ref "U3") (pin "N6") (pinfunction "SMPS6_IN_N6") (pintype "power_in"))
      (node (ref "U3") (pin "N8") (pinfunction "SMPS9_IN_N8") (pintype "power_in"))
      (node (ref "U3") (pin "N9") (pinfunction "SMPS8_IN_N9") (pintype "power_in"))
    )
    (net (code "21") (name "VDD_CORE") (class "Default")
      (node (ref "C266") (pin "1") (pinfunction "1_1") (pintype "passive"))
      (node (ref "C297") (pin "1") (pinfunction "1_1") (pintype "passive"))
      (node (ref "L20") (pin "2") (pinfunction "2_2") (pintype "passive"))
      (node (ref "U3") (pin "B1") (pinfunction "SMPS7_FDBK_B1") (pintype "passive"))
    )
    (net (code "22") (name "VDD_DDR") (class "Default")
      (node (ref "C295") (pin "1") (pinfunction "1_1") (pintype "passive"))
      (node (ref "C94") (pin "1") (pinfunction "1_1") (pintype "passive"))
      (node (ref "L16") (pin "2") (pinfunction "2_2") (pintype "passive"))
      (node (ref "U3") (pin "K13") (pinfunction "SMPS3_FDBK_K13") (pintype "passive"))
    )
    (net (code "23") (name "VDD_DSPEVE") (class "Default")
      (node (ref "C263") (pin "1") (pinfunction "1_1") (pintype "passive"))
      (node (ref "C265") (pin "1") (pinfunction "1_1") (pintype "passive"))
      (node (ref "L17") (pin "2") (pinfunction "2_2") (pintype "passive"))
      (node (ref "L18") (pin "2") (pinfunction "2_2") (pintype "passive"))
      (node (ref "U3") (pin "K2") (pinfunction "SMPS45_FDBK_K2") (pintype "passive"))
    )
    (net (code "24") (name "VDD_GPU") (class "Default")
      (node (ref "C264") (pin "1") (pinfunction "1_1") (pintype "passive"))
      (node (ref "L19") (pin "2") (pinfunction "2_2") (pintype "passive"))
      (node (ref "U3") (pin "K6") (pinfunction "SMPS6_FBK_K6") (pintype "power_in"))
    )
    (net (code "25") (name "VDD_IVA") (class "Default")
      (node (ref "C296") (pin "1") (pinfunction "1_1") (pintype "passive"))
      (node (ref "C93") (pin "1") (pinfunction "1_1") (pintype "passive"))
      (node (ref "L21") (pin "2") (pinfunction "2_2") (pintype "passive"))
      (node (ref "U3") (pin "L11") (pinfunction "SMPS8_FDBK_L11") (pintype "passive"))
    )
    (net (code "26") (name "VDD_MPU") (class "Default")
      (node (ref "C105") (pin "1") (pinfunction "1_1") (pintype "passive"))
      (node (ref "C111") (pin "1") (pinfunction "1_1") (pintype "passive"))
      (node (ref "L1") (pin "2") (pinfunction "2_2") (pintype "passive"))
      (node (ref "L2") (pin "2") (pinfunction "2_2") (pintype "passive"))
      (node (ref "U3") (pin "B13") (pinfunction "SMPS12_FBK_B13") (pintype "passive"))
    )
    (net (code "27") (name "unconnected-(ID1-Pad1)") (class "Default")
      (node (ref "ID1") (pin "1") (pinfunction "1_1") (pintype "input+no_connect"))
    )
    (net (code "28") (name "unconnected-(ID2-Pad1)") (class "Default")
      (node (ref "ID2") (pin "1") (pinfunction "1_1") (pintype "input+no_connect"))
    )
    (net (code "29") (name "unconnected-(ID3-Pad1)") (class "Default")
      (node (ref "ID3") (pin "1") (pinfunction "1_1") (pintype "input+no_connect"))
    )
  )
)
